# ByteBlasterII.net
KiCad netlist of a schematic drawn in EAGLE
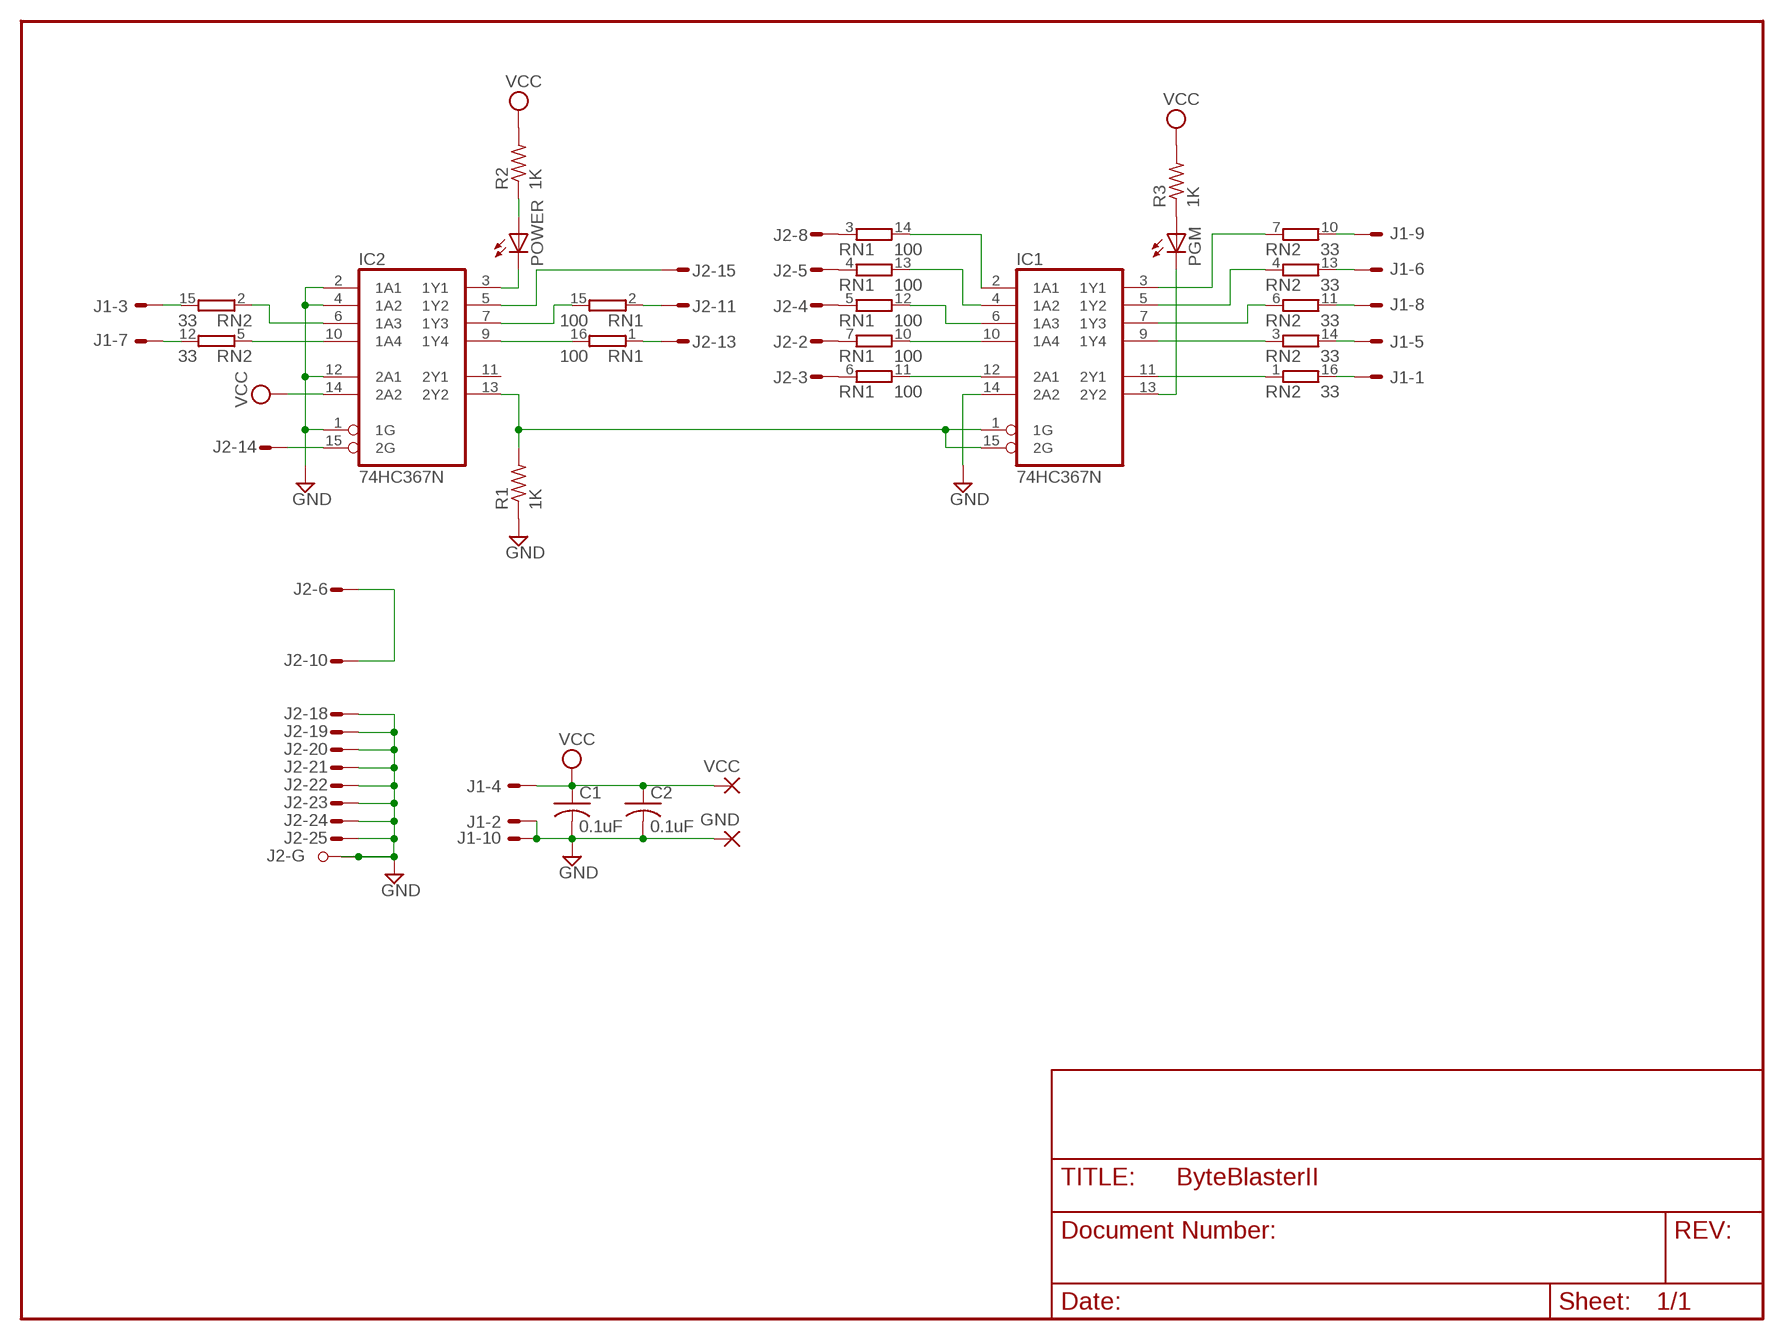
[diagram p0: schematic, sheet 1]

(export (version "E")
  (design (tool "Eeschema 10.0.6"))
  (components
    (comp (ref "C1")
      (value "0.1uF")
      (footprint "eagle-import:C050-025X075")
      (libsource (lib "eagle-import") (part "C-US050-025X075"))
    )
    (comp (ref "C2")
      (value "0.1uF")
      (footprint "eagle-import:C050-025X075")
      (libsource (lib "eagle-import") (part "C-US050-025X075"))
    )
    (comp (ref "GND")
      (value "1,6/0,9")
      (footprint "eagle-import:1,6_0,9")
      (libsource (lib "eagle-import") (part "1,6/0,9"))
    )
    (comp (ref "IC1")
      (value "74HC367N")
      (footprint "eagle-import:DIL16")
      (libsource (lib "eagle-import") (part "74367NHC"))
    )
    (comp (ref "IC2")
      (value "74HC367N")
      (footprint "eagle-import:DIL16")
      (libsource (lib "eagle-import") (part "74367NHC"))
    )
    (comp (ref "J1")
      (value "ML10E")
      (footprint "eagle-import:ML10")
      (libsource (lib "eagle-import") (part "ML10?E"))
    )
    (comp (ref "J2")
      (value "M25VPS")
      (footprint "eagle-import:M25VP")
      (libsource (lib "eagle-import") (part "M25VPS"))
    )
    (comp (ref "PGM")
      (value "LED3MM")
      (footprint "eagle-import:LED3MM")
      (libsource (lib "eagle-import") (part "LED3MM"))
    )
    (comp (ref "POWER")
      (value "LED3MM")
      (footprint "eagle-import:LED3MM")
      (libsource (lib "eagle-import") (part "LED3MM"))
    )
    (comp (ref "R1")
      (value "1K")
      (footprint "eagle-import:0207_10")
      (libsource (lib "eagle-import") (part "R-US_0207/10"))
    )
    (comp (ref "R2")
      (value "1K")
      (footprint "eagle-import:0207_10")
      (libsource (lib "eagle-import") (part "R-US_0207/10"))
    )
    (comp (ref "R3")
      (value "1K")
      (footprint "eagle-import:0207_10")
      (libsource (lib "eagle-import") (part "R-US_0207/10"))
    )
    (comp (ref "RN1")
      (value "100")
      (footprint "eagle-import:DIL16")
      (libsource (lib "eagle-import") (part "8R-P"))
    )
    (comp (ref "RN2")
      (value "33")
      (footprint "eagle-import:DIL16")
      (libsource (lib "eagle-import") (part "8R-P"))
    )
    (comp (ref "VCC")
      (value "1,6/0,9")
      (footprint "eagle-import:1,6_0,9")
      (libsource (lib "eagle-import") (part "1,6/0,9"))
    )
  )
  (nets
    (net (code "1") (name "GND") (class "Default")
      (node (ref "C1") (pin "2") (pinfunction "2_2") (pintype "passive"))
      (node (ref "C2") (pin "2") (pinfunction "2_2") (pintype "passive"))
      (node (ref "GND") (pin "1") (pinfunction "P_1") (pintype "passive"))
      (node (ref "IC1") (pin "14") (pinfunction "2A2_14") (pintype "input"))
      (node (ref "IC2") (pin "1") (pinfunction "1G_1") (pintype "input"))
      (node (ref "IC2") (pin "12") (pinfunction "2A1_12") (pintype "input"))
      (node (ref "IC2") (pin "2") (pinfunction "1A1_2") (pintype "input"))
      (node (ref "IC2") (pin "4") (pinfunction "1A2_4") (pintype "input"))
      (node (ref "J1") (pin "10") (pinfunction "S_10") (pintype "passive"))
      (node (ref "J1") (pin "2") (pinfunction "S_2") (pintype "passive"))
      (node (ref "J2") (pin "18") (pinfunction "M_18") (pintype "passive"))
      (node (ref "J2") (pin "19") (pinfunction "M_19") (pintype "passive"))
      (node (ref "J2") (pin "20") (pinfunction "M_20") (pintype "passive"))
      (node (ref "J2") (pin "21") (pinfunction "M_21") (pintype "passive"))
      (node (ref "J2") (pin "22") (pinfunction "M_22") (pintype "passive"))
      (node (ref "J2") (pin "23") (pinfunction "M_23") (pintype "passive"))
      (node (ref "J2") (pin "24") (pinfunction "M_24") (pintype "passive"))
      (node (ref "J2") (pin "25") (pinfunction "M_25") (pintype "passive"))
      (node (ref "J2") (pin "G1") (pinfunction "G1_G1") (pintype "passive"))
      (node (ref "J2") (pin "G2") (pinfunction "G2_G2") (pintype "passive"))
      (node (ref "R1") (pin "1") (pinfunction "1_1") (pintype "passive"))
    )
    (net (code "2") (name "Net-(IC1A-1A1)") (class "Default")
      (node (ref "IC1") (pin "2") (pinfunction "1A1_2") (pintype "input"))
      (node (ref "RN1") (pin "14") (pinfunction "2_14") (pintype "passive"))
    )
    (net (code "3") (name "Net-(IC1A-1A2)") (class "Default")
      (node (ref "IC1") (pin "4") (pinfunction "1A2_4") (pintype "input"))
      (node (ref "RN1") (pin "13") (pinfunction "2_13") (pintype "passive"))
    )
    (net (code "4") (name "Net-(IC1A-1A3)") (class "Default")
      (node (ref "IC1") (pin "6") (pinfunction "1A3_6") (pintype "input"))
      (node (ref "RN1") (pin "12") (pinfunction "2_12") (pintype "passive"))
    )
    (net (code "5") (name "Net-(IC1A-1A4)") (class "Default")
      (node (ref "IC1") (pin "10") (pinfunction "1A4_10") (pintype "input"))
      (node (ref "RN1") (pin "10") (pinfunction "2_10") (pintype "passive"))
    )
    (net (code "6") (name "Net-(IC1A-1G)") (class "Default")
      (node (ref "IC1") (pin "1") (pinfunction "1G_1") (pintype "input"))
      (node (ref "IC1") (pin "15") (pinfunction "2G_15") (pintype "input"))
      (node (ref "IC2") (pin "13") (pinfunction "2Y2_13") (pintype "tri_state"))
      (node (ref "R1") (pin "2") (pinfunction "2_2") (pintype "passive"))
    )
    (net (code "7") (name "Net-(IC1A-1Y1)") (class "Default")
      (node (ref "IC1") (pin "3") (pinfunction "1Y1_3") (pintype "tri_state"))
      (node (ref "RN2") (pin "7") (pinfunction "1_7") (pintype "passive"))
    )
    (net (code "8") (name "Net-(IC1A-1Y2)") (class "Default")
      (node (ref "IC1") (pin "5") (pinfunction "1Y2_5") (pintype "tri_state"))
      (node (ref "RN2") (pin "4") (pinfunction "1_4") (pintype "passive"))
    )
    (net (code "9") (name "Net-(IC1A-1Y3)") (class "Default")
      (node (ref "IC1") (pin "7") (pinfunction "1Y3_7") (pintype "tri_state"))
      (node (ref "RN2") (pin "6") (pinfunction "1_6") (pintype "passive"))
    )
    (net (code "10") (name "Net-(IC1A-1Y4)") (class "Default")
      (node (ref "IC1") (pin "9") (pinfunction "1Y4_9") (pintype "tri_state"))
      (node (ref "RN2") (pin "3") (pinfunction "1_3") (pintype "passive"))
    )
    (net (code "11") (name "Net-(IC1A-2A1)") (class "Default")
      (node (ref "IC1") (pin "12") (pinfunction "2A1_12") (pintype "input"))
      (node (ref "RN1") (pin "11") (pinfunction "2_11") (pintype "passive"))
    )
    (net (code "12") (name "Net-(IC1A-2Y1)") (class "Default")
      (node (ref "IC1") (pin "11") (pinfunction "2Y1_11") (pintype "tri_state"))
      (node (ref "RN2") (pin "1") (pinfunction "1_1") (pintype "passive"))
    )
    (net (code "13") (name "Net-(IC1A-2Y2)") (class "Default")
      (node (ref "IC1") (pin "13") (pinfunction "2Y2_13") (pintype "tri_state"))
      (node (ref "PGM") (pin "K") (pinfunction "C_K") (pintype "passive"))
    )
    (net (code "14") (name "Net-(IC2A-1A3)") (class "Default")
      (node (ref "IC2") (pin "6") (pinfunction "1A3_6") (pintype "input"))
      (node (ref "RN2") (pin "2") (pinfunction "1_2") (pintype "passive"))
    )
    (net (code "15") (name "Net-(IC2A-1A4)") (class "Default")
      (node (ref "IC2") (pin "10") (pinfunction "1A4_10") (pintype "input"))
      (node (ref "RN2") (pin "5") (pinfunction "1_5") (pintype "passive"))
    )
    (net (code "16") (name "Net-(IC2A-1Y1)") (class "Default")
      (node (ref "IC2") (pin "3") (pinfunction "1Y1_3") (pintype "tri_state"))
      (node (ref "POWER") (pin "K") (pinfunction "C_K") (pintype "passive"))
    )
    (net (code "17") (name "Net-(IC2A-1Y2)") (class "Default")
      (node (ref "IC2") (pin "5") (pinfunction "1Y2_5") (pintype "tri_state"))
      (node (ref "J2") (pin "15") (pinfunction "M_15") (pintype "passive"))
    )
    (net (code "18") (name "Net-(IC2A-1Y3)") (class "Default")
      (node (ref "IC2") (pin "7") (pinfunction "1Y3_7") (pintype "tri_state"))
      (node (ref "RN1") (pin "15") (pinfunction "2_15") (pintype "passive"))
    )
    (net (code "19") (name "Net-(IC2A-1Y4)") (class "Default")
      (node (ref "IC2") (pin "9") (pinfunction "1Y4_9") (pintype "tri_state"))
      (node (ref "RN1") (pin "16") (pinfunction "2_16") (pintype "passive"))
    )
    (net (code "20") (name "Net-(IC2A-2G)") (class "Default")
      (node (ref "IC2") (pin "15") (pinfunction "2G_15") (pintype "input"))
      (node (ref "J2") (pin "14") (pinfunction "M_14") (pintype "passive"))
    )
    (net (code "21") (name "Net-(J1A-S)") (class "Default")
      (node (ref "J1") (pin "1") (pinfunction "S_1") (pintype "passive"))
      (node (ref "RN2") (pin "16") (pinfunction "2_16") (pintype "passive"))
    )
    (net (code "22") (name "Net-(J1D-S)") (class "Default")
      (node (ref "J1") (pin "3") (pinfunction "S_3") (pintype "passive"))
      (node (ref "RN2") (pin "15") (pinfunction "2_15") (pintype "passive"))
    )
    (net (code "23") (name "Net-(J1F-S)") (class "Default")
      (node (ref "J1") (pin "5") (pinfunction "S_5") (pintype "passive"))
      (node (ref "RN2") (pin "14") (pinfunction "2_14") (pintype "passive"))
    )
    (net (code "24") (name "Net-(J1G-S)") (class "Default")
      (node (ref "J1") (pin "6") (pinfunction "S_6") (pintype "passive"))
      (node (ref "RN2") (pin "13") (pinfunction "2_13") (pintype "passive"))
    )
    (net (code "25") (name "Net-(J1H-S)") (class "Default")
      (node (ref "J1") (pin "7") (pinfunction "S_7") (pintype "passive"))
      (node (ref "RN2") (pin "12") (pinfunction "2_12") (pintype "passive"))
    )
    (net (code "26") (name "Net-(J1I-S)") (class "Default")
      (node (ref "J1") (pin "8") (pinfunction "S_8") (pintype "passive"))
      (node (ref "RN2") (pin "11") (pinfunction "2_11") (pintype "passive"))
    )
    (net (code "27") (name "Net-(J1J-S)") (class "Default")
      (node (ref "J1") (pin "9") (pinfunction "S_9") (pintype "passive"))
      (node (ref "RN2") (pin "10") (pinfunction "2_10") (pintype "passive"))
    )
    (net (code "28") (name "Net-(J2B-M)") (class "Default")
      (node (ref "J2") (pin "10") (pinfunction "M_10") (pintype "passive"))
      (node (ref "J2") (pin "6") (pinfunction "M_6") (pintype "passive"))
    )
    (net (code "29") (name "Net-(J2C-M)") (class "Default")
      (node (ref "J2") (pin "11") (pinfunction "M_11") (pintype "passive"))
      (node (ref "RN1") (pin "2") (pinfunction "1_2") (pintype "passive"))
    )
    (net (code "30") (name "Net-(J2E-M)") (class "Default")
      (node (ref "J2") (pin "13") (pinfunction "M_13") (pintype "passive"))
      (node (ref "RN1") (pin "1") (pinfunction "1_1") (pintype "passive"))
    )
    (net (code "31") (name "Net-(J2L-M)") (class "Default")
      (node (ref "J2") (pin "2") (pinfunction "M_2") (pintype "passive"))
      (node (ref "RN1") (pin "7") (pinfunction "1_7") (pintype "passive"))
    )
    (net (code "32") (name "Net-(J2S-M)") (class "Default")
      (node (ref "J2") (pin "3") (pinfunction "M_3") (pintype "passive"))
      (node (ref "RN1") (pin "6") (pinfunction "1_6") (pintype "passive"))
    )
    (net (code "33") (name "Net-(J2T-M)") (class "Default")
      (node (ref "J2") (pin "4") (pinfunction "M_4") (pintype "passive"))
      (node (ref "RN1") (pin "5") (pinfunction "1_5") (pintype "passive"))
    )
    (net (code "34") (name "Net-(J2U-M)") (class "Default")
      (node (ref "J2") (pin "5") (pinfunction "M_5") (pintype "passive"))
      (node (ref "RN1") (pin "4") (pinfunction "1_4") (pintype "passive"))
    )
    (net (code "35") (name "Net-(J2X-M)") (class "Default")
      (node (ref "J2") (pin "8") (pinfunction "M_8") (pintype "passive"))
      (node (ref "RN1") (pin "3") (pinfunction "1_3") (pintype "passive"))
    )
    (net (code "36") (name "Net-(PGM-PadA)") (class "Default")
      (node (ref "PGM") (pin "A") (pinfunction "A_A") (pintype "passive"))
      (node (ref "R3") (pin "1") (pinfunction "1_1") (pintype "passive"))
    )
    (net (code "37") (name "Net-(POWER-PadA)") (class "Default")
      (node (ref "POWER") (pin "A") (pinfunction "A_A") (pintype "passive"))
      (node (ref "R2") (pin "1") (pinfunction "1_1") (pintype "passive"))
    )
    (net (code "38") (name "VCC") (class "Default")
      (node (ref "C1") (pin "1") (pinfunction "1_1") (pintype "passive"))
      (node (ref "C2") (pin "1") (pinfunction "1_1") (pintype "passive"))
      (node (ref "IC2") (pin "14") (pinfunction "2A2_14") (pintype "input"))
      (node (ref "J1") (pin "4") (pinfunction "S_4") (pintype "passive"))
      (node (ref "R2") (pin "2") (pinfunction "2_2") (pintype "passive"))
      (node (ref "R3") (pin "2") (pinfunction "2_2") (pintype "passive"))
      (node (ref "VCC") (pin "1") (pinfunction "P_1") (pintype "passive"))
    )
    (net (code "39") (name "unconnected-(IC2A-2Y1-Pad11)") (class "Default")
      (node (ref "IC2") (pin "11") (pinfunction "2Y1_11") (pintype "tri_state"))
    )
  )
)
